# LoRa-Bee_v10.net
KiCad netlist of a schematic drawn in EAGLE
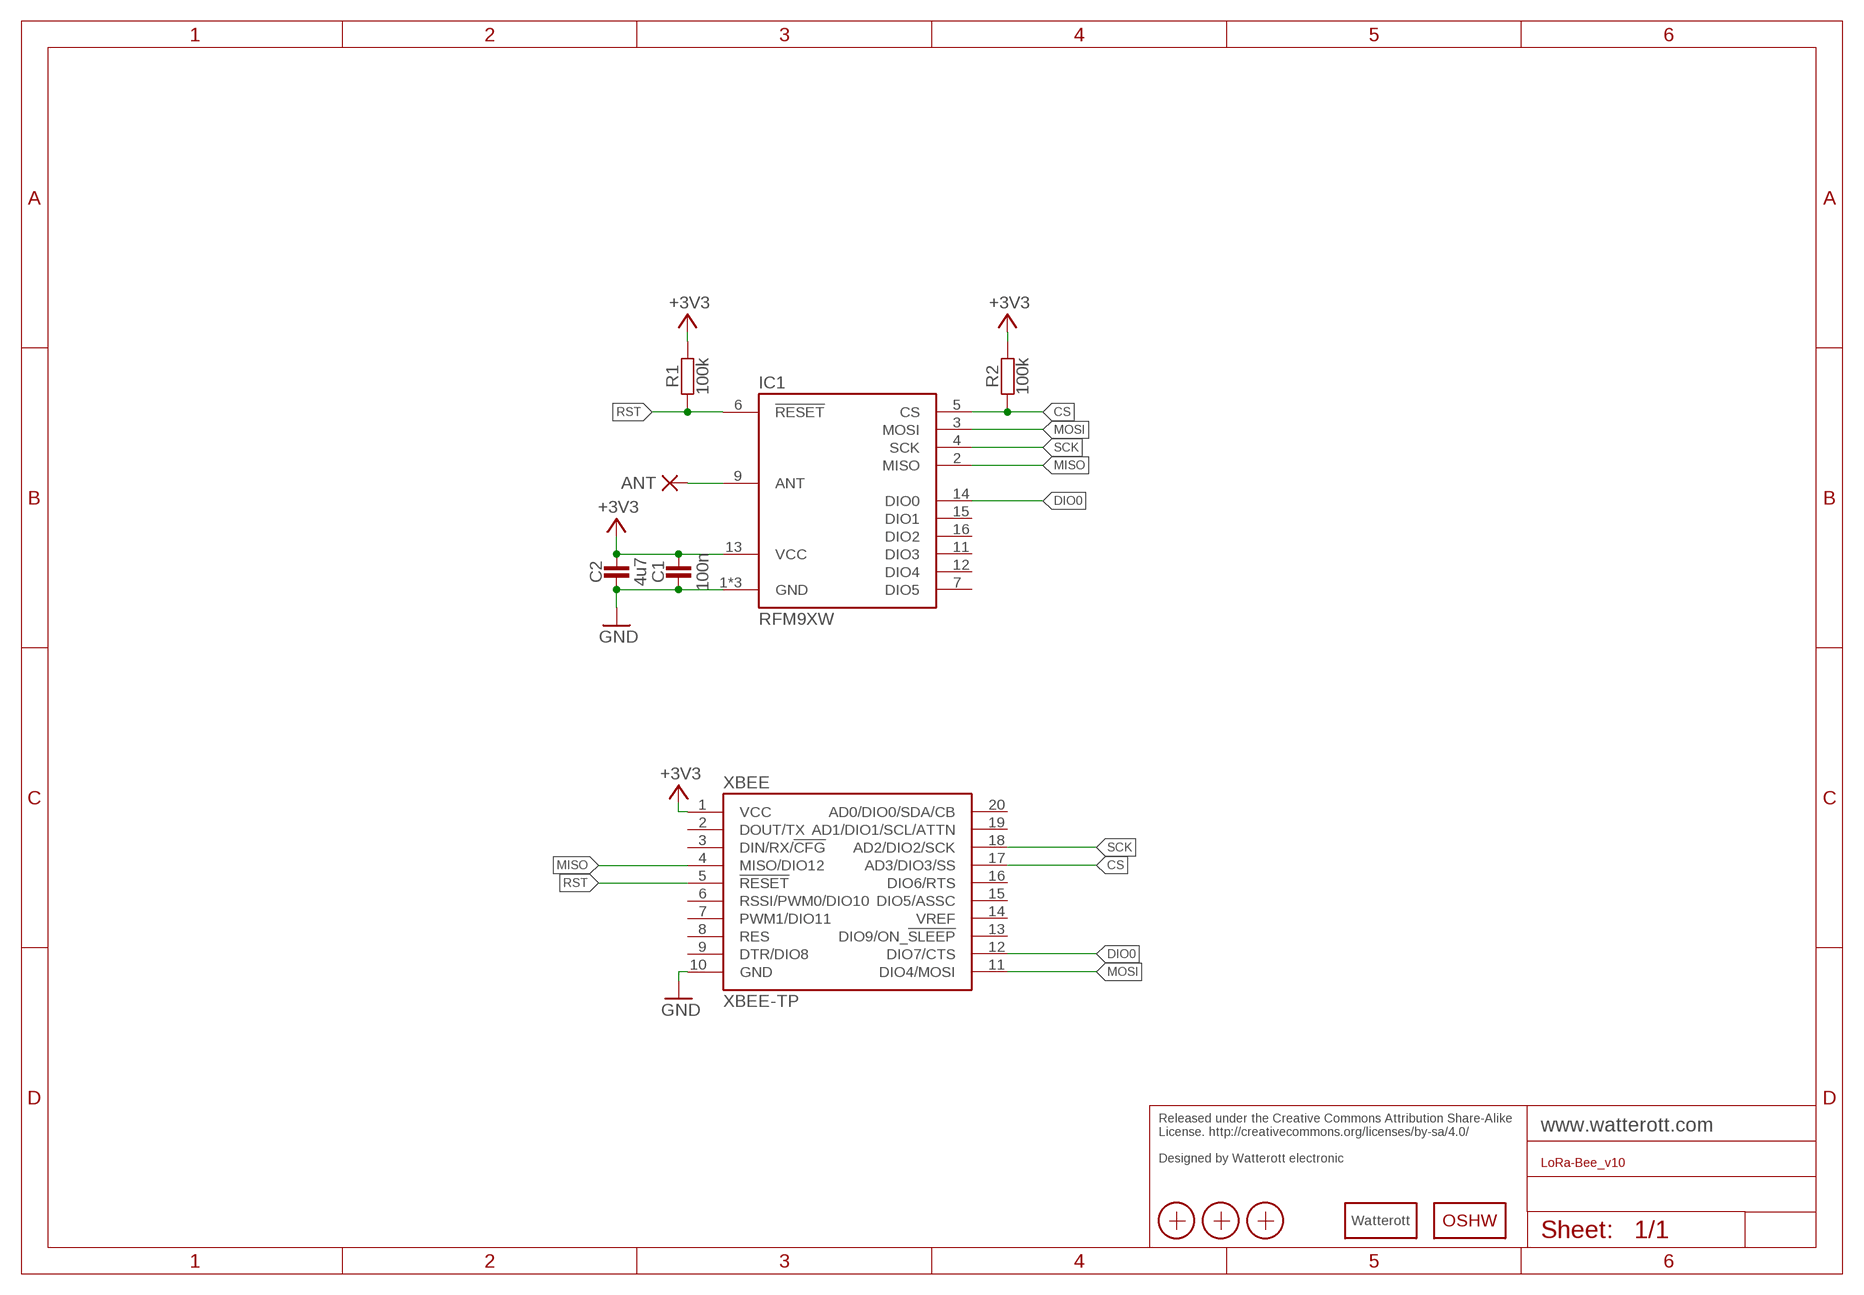
[diagram p0: schematic, sheet 1]

(export (version "E")
  (design (tool "Eeschema 10.0.6"))
  (components
    (comp (ref "ANT")
      (value "PAD-1.00-1.60")
      (footprint "eagle-import:PAD-1.00-1.60")
      (libsource (lib "eagle-import") (part "PAD-1.00-1.60"))
    )
    (comp (ref "C1")
      (value "100n")
      (footprint "eagle-import:C0402")
      (libsource (lib "eagle-import") (part "CAPACITOR-0402"))
    )
    (comp (ref "C2")
      (value "4u7")
      (footprint "eagle-import:C0402")
      (libsource (lib "eagle-import") (part "CAPACITOR-0402"))
    )
    (comp (ref "IC1")
      (value "RFM9XW")
      (footprint "eagle-import:RFM9X")
      (libsource (lib "eagle-import") (part "RFM9XW"))
    )
    (comp (ref "LOGO2")
      (value "OSHW_LOGOX0070")
      (footprint "eagle-import:OSHW_6X70")
      (libsource (lib "eagle-import") (part "OSHW_LOGOX0070"))
    )
    (comp (ref "LOGO3")
      (value "LOGO_SPARK-2")
      (footprint "eagle-import:SPARK_2MM")
      (libsource (lib "eagle-import") (part "LOGO_SPARK-2"))
    )
    (comp (ref "R1")
      (value "100k")
      (footprint "eagle-import:C0402")
      (libsource (lib "eagle-import") (part "RESISTOR-0402"))
    )
    (comp (ref "R2")
      (value "100k")
      (footprint "eagle-import:C0402")
      (libsource (lib "eagle-import") (part "RESISTOR-0402"))
    )
    (comp (ref "X1")
      (value "PASSER-07")
      (footprint "eagle-import:PASSER_07MM")
      (libsource (lib "eagle-import") (part "PASSER-07"))
    )
    (comp (ref "X2")
      (value "PASSER-07")
      (footprint "eagle-import:PASSER_07MM")
      (libsource (lib "eagle-import") (part "PASSER-07"))
    )
    (comp (ref "X3")
      (value "PASSER-07")
      (footprint "eagle-import:PASSER_07MM")
      (libsource (lib "eagle-import") (part "PASSER-07"))
    )
    (comp (ref "XBEE")
      (value "XBEE-TP")
      (footprint "eagle-import:XBEE_TP")
      (libsource (lib "eagle-import") (part "XBEE-TP"))
    )
  )
  (nets
    (net (code "1") (name "+3V3") (class "Default")
      (node (ref "C1") (pin "2") (pinfunction "2_2") (pintype "passive"))
      (node (ref "C2") (pin "2") (pinfunction "2_2") (pintype "passive"))
      (node (ref "IC1") (pin "13") (pinfunction "VCC_13") (pintype "power_in"))
      (node (ref "R1") (pin "2") (pinfunction "2_2") (pintype "passive"))
      (node (ref "R2") (pin "2") (pinfunction "2_2") (pintype "passive"))
      (node (ref "XBEE") (pin "1") (pinfunction "VCC_1") (pintype "power_in"))
    )
    (net (code "2") (name "CS") (class "Default")
      (node (ref "IC1") (pin "5") (pinfunction "CS_5") (pintype "input"))
      (node (ref "R2") (pin "1") (pinfunction "1_1") (pintype "passive"))
      (node (ref "XBEE") (pin "17") (pinfunction "AD3/DIO3/SS_17") (pintype "bidirectional"))
    )
    (net (code "3") (name "DIO0") (class "Default")
      (node (ref "IC1") (pin "14") (pinfunction "DIO0_14") (pintype "bidirectional"))
      (node (ref "XBEE") (pin "12") (pinfunction "DIO7/CTS_12") (pintype "bidirectional"))
    )
    (net (code "4") (name "GND") (class "Default")
      (node (ref "C1") (pin "1") (pinfunction "1_1") (pintype "passive"))
      (node (ref "C2") (pin "1") (pinfunction "1_1") (pintype "passive"))
      (node (ref "IC1") (pin "1") (pinfunction "GND_1") (pintype "power_in"))
      (node (ref "IC1") (pin "10") (pinfunction "GND_10") (pintype "power_in"))
      (node (ref "IC1") (pin "8") (pinfunction "GND_8") (pintype "power_in"))
      (node (ref "XBEE") (pin "10") (pinfunction "GND_10") (pintype "power_in"))
    )
    (net (code "5") (name "MISO") (class "Default")
      (node (ref "IC1") (pin "2") (pinfunction "MISO_2") (pintype "output"))
      (node (ref "XBEE") (pin "4") (pinfunction "MISO/DIO12_4") (pintype "bidirectional"))
    )
    (net (code "6") (name "MOSI") (class "Default")
      (node (ref "IC1") (pin "3") (pinfunction "MOSI_3") (pintype "input"))
      (node (ref "XBEE") (pin "11") (pinfunction "DIO4/MOSI_11") (pintype "bidirectional"))
    )
    (net (code "7") (name "Net-(ANT-P)") (class "Default")
      (node (ref "ANT") (pin "1") (pinfunction "P_1") (pintype "passive"))
      (node (ref "IC1") (pin "9") (pinfunction "ANT_9") (pintype "bidirectional"))
    )
    (net (code "8") (name "RST") (class "Default")
      (node (ref "IC1") (pin "6") (pinfunction "~{RESET}_6") (pintype "input"))
      (node (ref "R1") (pin "1") (pinfunction "1_1") (pintype "passive"))
      (node (ref "XBEE") (pin "5") (pinfunction "~{RESET}_5") (pintype "bidirectional"))
    )
    (net (code "9") (name "SCK") (class "Default")
      (node (ref "IC1") (pin "4") (pinfunction "SCK_4") (pintype "input"))
      (node (ref "XBEE") (pin "18") (pinfunction "AD2/DIO2/SCK_18") (pintype "bidirectional"))
    )
    (net (code "10") (name "unconnected-(IC1-DIO1-Pad15)") (class "Default")
      (node (ref "IC1") (pin "15") (pinfunction "DIO1_15") (pintype "bidirectional"))
    )
    (net (code "11") (name "unconnected-(IC1-DIO2-Pad16)") (class "Default")
      (node (ref "IC1") (pin "16") (pinfunction "DIO2_16") (pintype "bidirectional"))
    )
    (net (code "12") (name "unconnected-(IC1-DIO3-Pad11)") (class "Default")
      (node (ref "IC1") (pin "11") (pinfunction "DIO3_11") (pintype "bidirectional"))
    )
    (net (code "13") (name "unconnected-(IC1-DIO4-Pad12)") (class "Default")
      (node (ref "IC1") (pin "12") (pinfunction "DIO4_12") (pintype "bidirectional"))
    )
    (net (code "14") (name "unconnected-(IC1-DIO5-Pad7)") (class "Default")
      (node (ref "IC1") (pin "7") (pinfunction "DIO5_7") (pintype "bidirectional"))
    )
    (net (code "15") (name "unconnected-(XBEE-AD0{slash}DIO0{slash}SDA{slash}CB-Pad20)") (class "Default")
      (node (ref "XBEE") (pin "20") (pinfunction "AD0/DIO0/SDA/CB_20") (pintype "bidirectional"))
    )
    (net (code "16") (name "unconnected-(XBEE-AD1{slash}DIO1{slash}SCL{slash}ATTN-Pad19)") (class "Default")
      (node (ref "XBEE") (pin "19") (pinfunction "AD1/DIO1/SCL/ATTN_19") (pintype "bidirectional"))
    )
    (net (code "17") (name "unconnected-(XBEE-DIN{slash}RX{slash}~{CFG}-Pad3)") (class "Default")
      (node (ref "XBEE") (pin "3") (pinfunction "DIN/RX/~{CFG}_3") (pintype "bidirectional"))
    )
    (net (code "18") (name "unconnected-(XBEE-DIO5{slash}ASSC-Pad15)") (class "Default")
      (node (ref "XBEE") (pin "15") (pinfunction "DIO5/ASSC_15") (pintype "bidirectional"))
    )
    (net (code "19") (name "unconnected-(XBEE-DIO6{slash}RTS-Pad16)") (class "Default")
      (node (ref "XBEE") (pin "16") (pinfunction "DIO6/RTS_16") (pintype "bidirectional"))
    )
    (net (code "20") (name "unconnected-(XBEE-DIO9{slash}ON_~{SLEEP}-Pad13)") (class "Default")
      (node (ref "XBEE") (pin "13") (pinfunction "DIO9/ON_~{SLEEP}_13") (pintype "bidirectional"))
    )
    (net (code "21") (name "unconnected-(XBEE-DOUT{slash}TX-Pad2)") (class "Default")
      (node (ref "XBEE") (pin "2") (pinfunction "DOUT/TX_2") (pintype "bidirectional"))
    )
    (net (code "22") (name "unconnected-(XBEE-DTR{slash}DIO8-Pad9)") (class "Default")
      (node (ref "XBEE") (pin "9") (pinfunction "DTR/DIO8_9") (pintype "bidirectional"))
    )
    (net (code "23") (name "unconnected-(XBEE-PWM1{slash}DIO11-Pad7)") (class "Default")
      (node (ref "XBEE") (pin "7") (pinfunction "PWM1/DIO11_7") (pintype "bidirectional"))
    )
    (net (code "24") (name "unconnected-(XBEE-RES-Pad8)") (class "Default")
      (node (ref "XBEE") (pin "8") (pinfunction "RES_8") (pintype "bidirectional"))
    )
    (net (code "25") (name "unconnected-(XBEE-RSSI{slash}PWM0{slash}DIO10-Pad6)") (class "Default")
      (node (ref "XBEE") (pin "6") (pinfunction "RSSI/PWM0/DIO10_6") (pintype "bidirectional"))
    )
    (net (code "26") (name "unconnected-(XBEE-VREF-Pad14)") (class "Default")
      (node (ref "XBEE") (pin "14") (pinfunction "VREF_14") (pintype "bidirectional"))
    )
  )
)
